# sensor_board_v0_9.net
KiCad netlist of a schematic drawn in EAGLE
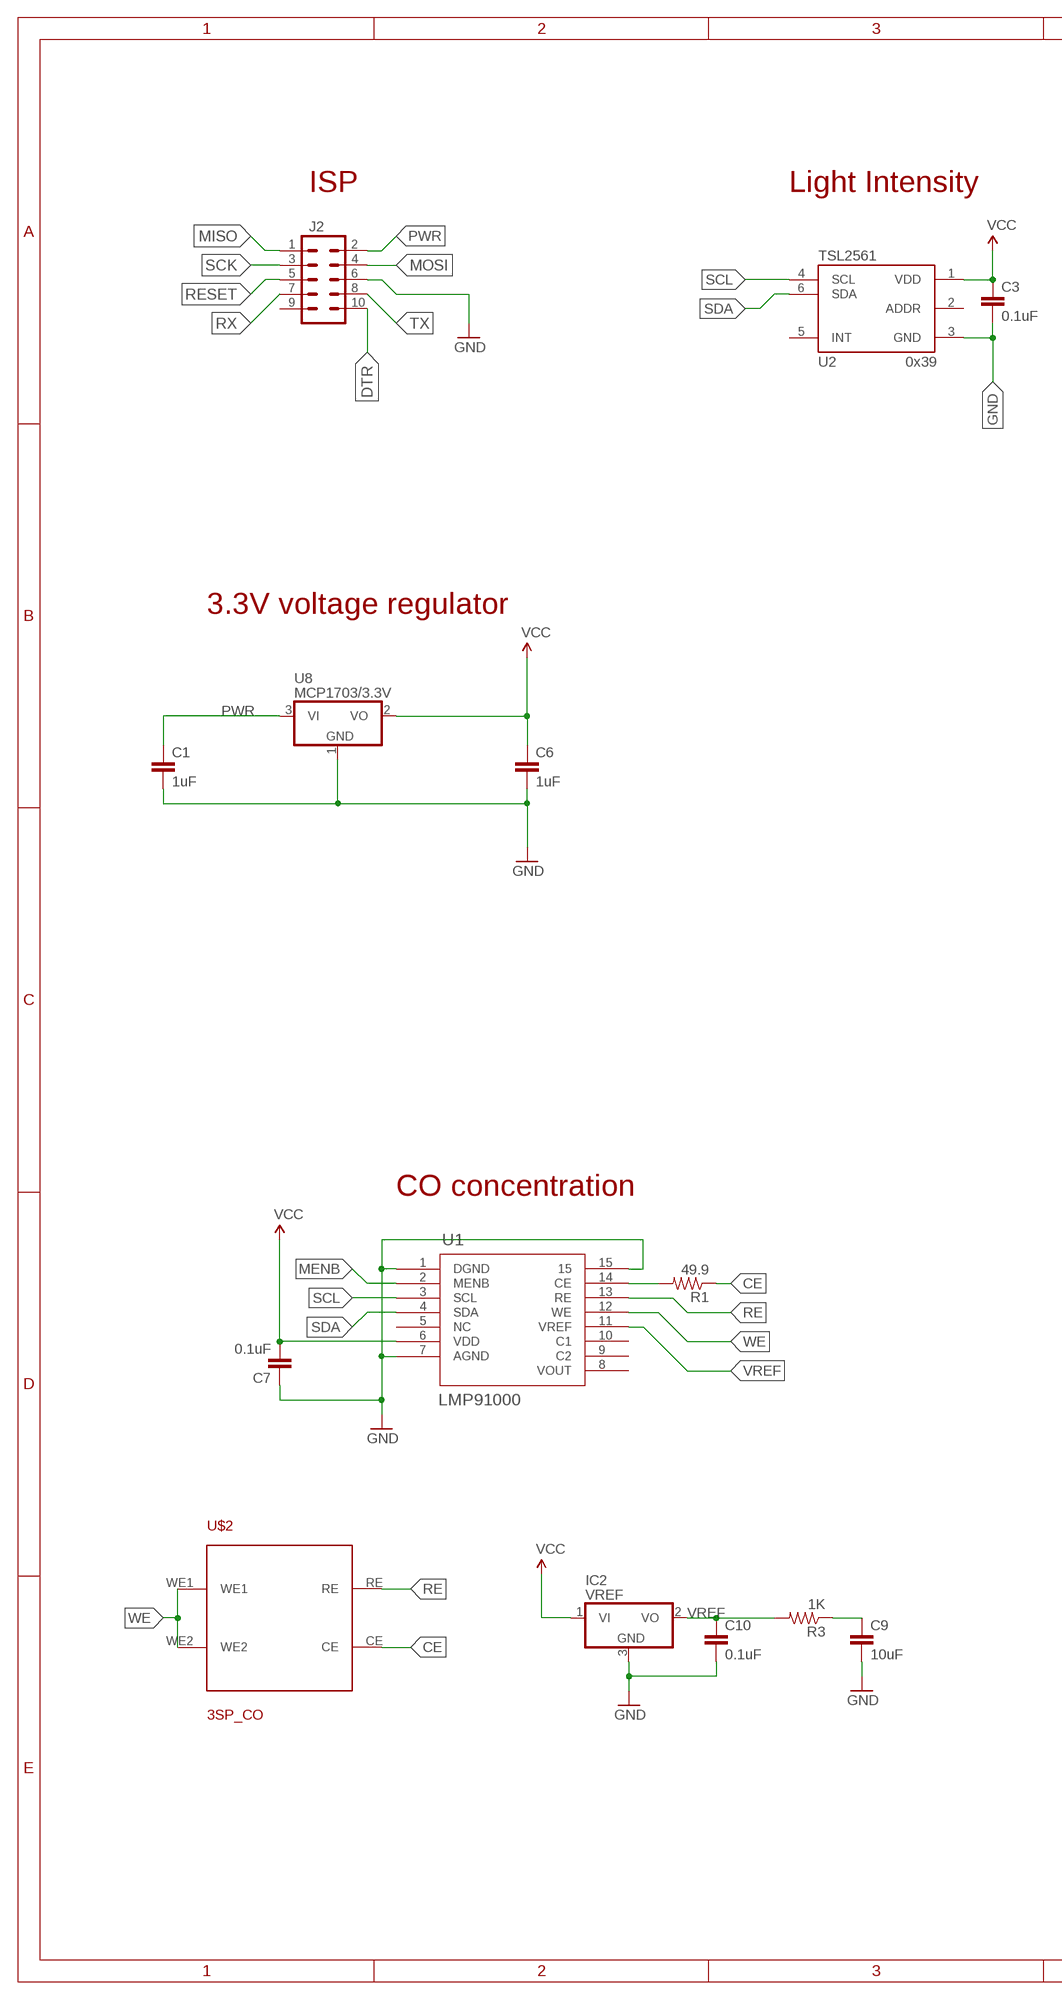
[diagram p0: schematic, sheet 1, part 1 of 2]
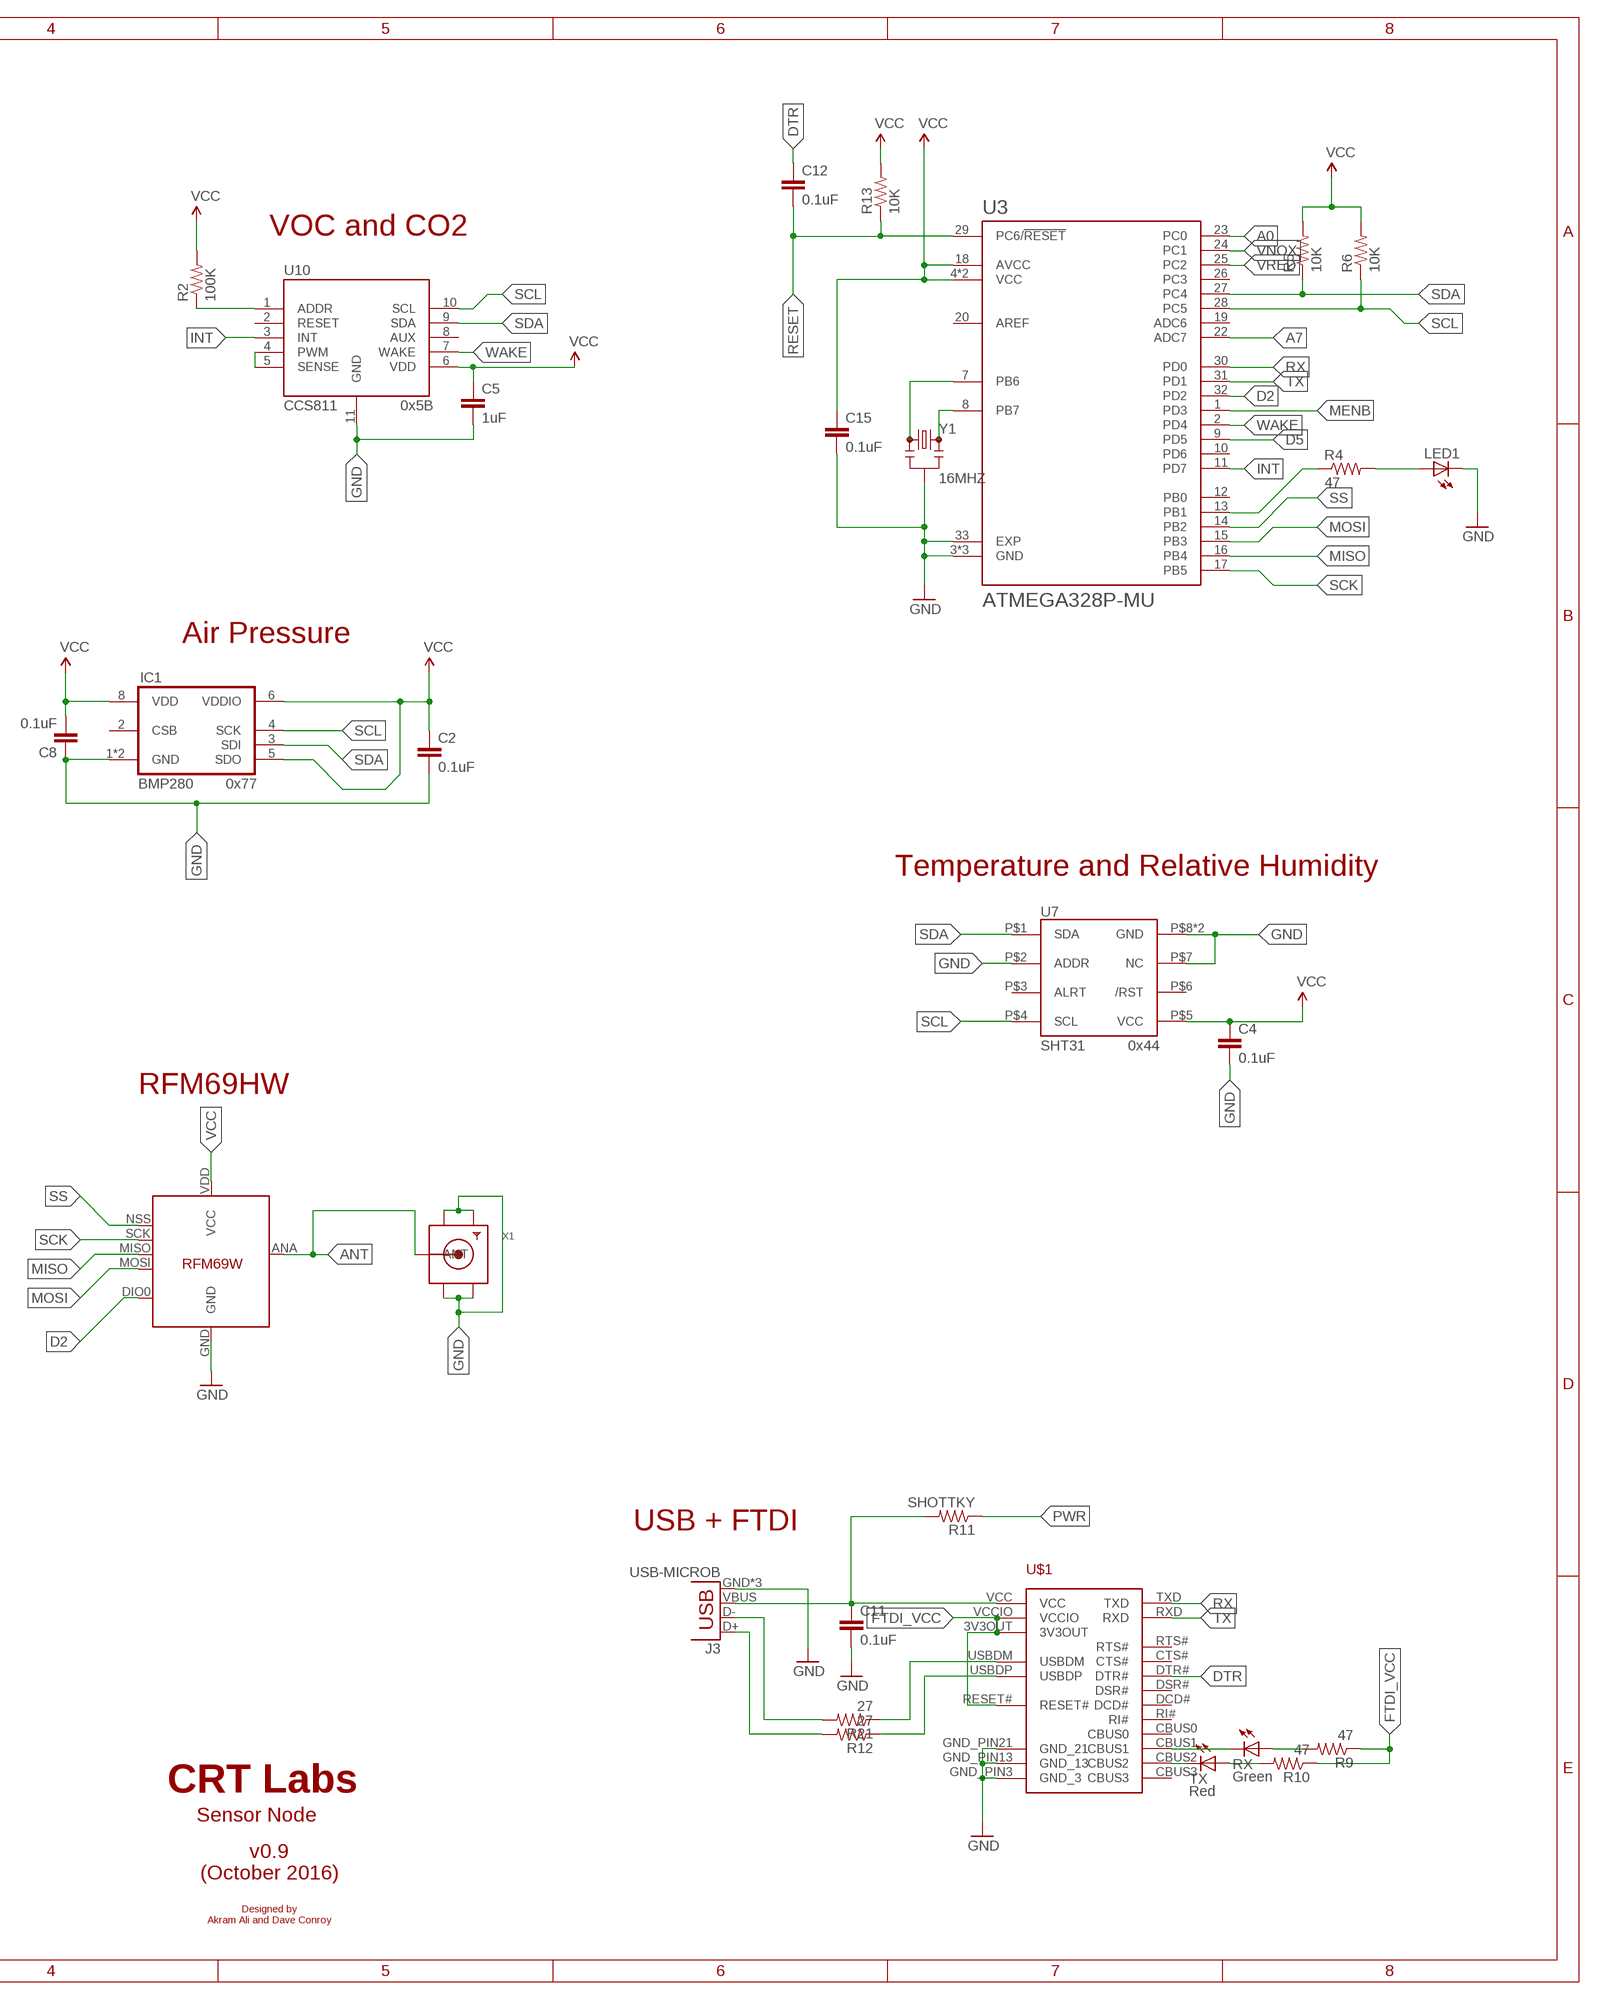
[diagram p1: schematic, sheet 1, part 2 of 2]

(export (version "E")
  (design (tool "Eeschema 10.0.6"))
  (components
    (comp (ref "C1")
      (value "1uF")
      (footprint "eagle-import:0805")
      (fields (field (name "MPN") "CC0805KKX7R7BB105"))
      (libsource (lib "eagle-import") (part "CAP0805"))
    )
    (comp (ref "C2")
      (value "0.1uF")
      (footprint "eagle-import:0805")
      (fields (field (name "MPN") "AC0805KRX7R9BB104"))
      (libsource (lib "eagle-import") (part "SparkFun-Passives_CAP0805"))
    )
    (comp (ref "C3")
      (value "0.1uF")
      (footprint "eagle-import:0805")
      (fields (field (name "MPN") "AC0805KRX7R9BB104"))
      (libsource (lib "eagle-import") (part "SparkFun-Passives_CAP0805"))
    )
    (comp (ref "C4")
      (value "0.1uF")
      (footprint "eagle-import:0805")
      (fields (field (name "MPN") "AC0805KRX7R9BB104"))
      (libsource (lib "eagle-import") (part "SparkFun-Passives_CAP0805"))
    )
    (comp (ref "C5")
      (value "1uF")
      (footprint "eagle-import:0805")
      (fields (field (name "MPN") "CC0805KKX7R7BB105"))
      (libsource (lib "eagle-import") (part "SparkFun-Passives_CAP0805"))
    )
    (comp (ref "C6")
      (value "1uF")
      (footprint "eagle-import:0805")
      (fields (field (name "MPN") "CC0805KKX7R7BB105"))
      (libsource (lib "eagle-import") (part "CAP0805"))
    )
    (comp (ref "C7")
      (value "0.1uF")
      (footprint "eagle-import:0805")
      (fields (field (name "MPN") "AC0805KRX7R9BB104"))
      (libsource (lib "eagle-import") (part "SparkFun-Passives_CAP0805"))
    )
    (comp (ref "C8")
      (value "0.1uF")
      (footprint "eagle-import:0805")
      (fields (field (name "MPN") "AC0805KRX7R9BB104"))
      (libsource (lib "eagle-import") (part "SparkFun-Passives_CAP0805"))
    )
    (comp (ref "C9")
      (value "10uF")
      (footprint "eagle-import:0805")
      (fields (field (name "MPN") "CC0805ZKY5V6BB106"))
      (libsource (lib "eagle-import") (part "SparkFun-Passives_CAP0805"))
    )
    (comp (ref "C10")
      (value "0.1uF")
      (footprint "eagle-import:0805")
      (fields (field (name "MPN") "AC0805KRX7R9BB104"))
      (libsource (lib "eagle-import") (part "SparkFun-Passives_CAP0805"))
    )
    (comp (ref "C11")
      (value "0.1uF")
      (footprint "eagle-import:0805")
      (fields (field (name "MPN") "AC0805KRX7R9BB104"))
      (libsource (lib "eagle-import") (part "CAP0805"))
    )
    (comp (ref "C12")
      (value "0.1uF")
      (footprint "eagle-import:0805")
      (fields (field (name "MPN") "AC0805KRX7R9BB104"))
      (libsource (lib "eagle-import") (part "SparkFun-Passives_CAP0805"))
    )
    (comp (ref "C15")
      (value "0.1uF")
      (footprint "eagle-import:0805")
      (fields (field (name "MPN") "AC0805KRX7R9BB104"))
      (libsource (lib "eagle-import") (part "SparkFun-Passives_CAP0805"))
    )
    (comp (ref "IC1")
      (value "BMP280")
      (footprint "eagle-import:BMP280")
      (libsource (lib "eagle-import") (part "BMP280"))
    )
    (comp (ref "IC2")
      (value "VREF")
      (footprint "eagle-import:SOT23")
      (fields (field (name "MPN") "ISL60002DIH320Z-TK"))
      (libsource (lib "eagle-import") (part "ISL60002DIH320ZCB"))
    )
    (comp (ref "J2")
      (value "M05X2PTH")
      (footprint "eagle-import:AVR_ICSP")
      (libsource (lib "eagle-import") (part "M05X2PTH"))
    )
    (comp (ref "J3")
      (value "USB-MICROB")
      (footprint "eagle-import:USB-MICROB")
      (fields (field (name "MPN") "CONN-09505"))
      (libsource (lib "eagle-import") (part "USB-MICROB"))
    )
    (comp (ref "LED1")
      (value "LEDCHIPLED_0805")
      (footprint "eagle-import:CHIPLED_0805")
      (fields (field (name "MPN") "150080BS75000"))
      (libsource (lib "eagle-import") (part "LEDCHIPLED_0805"))
    )
    (comp (ref "R1")
      (value "49.9")
      (footprint "eagle-import:0805")
      (fields (field (name "MPN") "RC0805FR-0749R9L"))
      (libsource (lib "eagle-import") (part "RESISTOR0805-RES"))
    )
    (comp (ref "R2")
      (value "100K")
      (footprint "eagle-import:0805")
      (fields (field (name "MPN") "311-100KCRCT-ND"))
      (libsource (lib "eagle-import") (part "RESISTOR0805-RES"))
    )
    (comp (ref "R3")
      (value "1K")
      (footprint "eagle-import:0805")
      (fields (field (name "MPN") "RC0805JR-071KL"))
      (libsource (lib "eagle-import") (part "RESISTOR0805-RES"))
    )
    (comp (ref "R4")
      (value "47")
      (footprint "eagle-import:0805")
      (fields (field (name "MPN") "RC0805JR-0747RL"))
      (libsource (lib "eagle-import") (part "SparkFun-Resistors_RESISTOR0805-RES"))
    )
    (comp (ref "R5")
      (value "10K")
      (footprint "eagle-import:0805")
      (fields (field (name "MPN") "RC0805JR-0710KL"))
      (libsource (lib "eagle-import") (part "SparkFun-Resistors_RESISTOR0805-RES"))
    )
    (comp (ref "R6")
      (value "10K")
      (footprint "eagle-import:0805")
      (fields (field (name "MPN") "RC0805JR-0710KL"))
      (libsource (lib "eagle-import") (part "SparkFun-Resistors_RESISTOR0805-RES"))
    )
    (comp (ref "R9")
      (value "47")
      (footprint "eagle-import:0805")
      (fields (field (name "MPN") "RC0805JR-0747RL"))
      (libsource (lib "eagle-import") (part "RESISTOR0805-RES"))
    )
    (comp (ref "R10")
      (value "47")
      (footprint "eagle-import:0805")
      (fields (field (name "MPN") "RC0805JR-0747RL"))
      (libsource (lib "eagle-import") (part "RESISTOR0805-RES"))
    )
    (comp (ref "R11")
      (value "SHOTTKY")
      (footprint "eagle-import:0805")
      (fields (field (name "MPN") "SD0805S020S0R5"))
      (libsource (lib "eagle-import") (part "RESISTOR0805-RES"))
    )
    (comp (ref "R12")
      (value "27")
      (footprint "eagle-import:0805")
      (fields (field (name "MPN") "RC0805FR-0727RL"))
      (libsource (lib "eagle-import") (part "RESISTOR0805-RES"))
    )
    (comp (ref "R13")
      (value "10K")
      (footprint "eagle-import:0805")
      (fields (field (name "MPN") "RC0805JR-0710KL"))
      (libsource (lib "eagle-import") (part "RESISTOR0805-RES"))
    )
    (comp (ref "R21")
      (value "27")
      (footprint "eagle-import:0805")
      (fields (field (name "MPN") "RC0805FR-0727RL"))
      (libsource (lib "eagle-import") (part "RESISTOR0805-RES"))
    )
    (comp (ref "RX")
      (value "Green")
      (footprint "eagle-import:CHIPLED_0805")
      (fields (field (name "MPN") "LG R971-KN-1"))
      (libsource (lib "eagle-import") (part "LEDCHIPLED_0805"))
    )
    (comp (ref "TX")
      (value "Red")
      (footprint "eagle-import:CHIPLED_0805")
      (fields (field (name "MPN") "LH R974-LP-1"))
      (libsource (lib "eagle-import") (part "LEDCHIPLED_0805"))
    )
    (comp (ref "U$1")
      (value "FT231XQ-R")
      (footprint "eagle-import:FTDI_FT231XQ-R_PACKAGE")
      (libsource (lib "eagle-import") (part "FT231XQ-R"))
    )
    (comp (ref "U$2")
      (value "3SP_CO")
      (footprint "eagle-import:3SP_CO_PIN_PACKAGE")
      (fields (field (name "MPN") "3SP CO"))
      (libsource (lib "eagle-import") (part "3SP_CO"))
    )
    (comp (ref "U1")
      (value "LMP91000")
      (footprint "eagle-import:SDA14B")
      (fields
        (field (name "MANUFACTURER") "Texas Instruments")
        (field (name "MANUFACTURER_PART_NUMBER") "lmp91000_nhl_14")
      )
      (libsource (lib "eagle-import") (part "LMP91000_NHL_14"))
    )
    (comp (ref "U2")
      (value "TSL2561")
      (footprint "eagle-import:FN-6")
      (fields (field (name "MPN") "TSL2561FN"))
      (libsource (lib "eagle-import") (part "TSL2561FN"))
    )
    (comp (ref "U3")
      (value "ATMEGA328P-MU")
      (footprint "eagle-import:QFN50P500X500X100-33N")
      (fields (field (name "MF") "Atmel"))
      (libsource (lib "eagle-import") (part "ATMEGA328P-MU"))
    )
    (comp (ref "U7")
      (value "SHT31")
      (footprint "eagle-import:SHT3X")
      (fields (field (name "MPN") "SHT31-DIS-B"))
      (libsource (lib "eagle-import") (part "SHT31-DIS"))
    )
    (comp (ref "U8")
      (value "MCP1703/3.3V")
      (footprint "eagle-import:SOT23")
      (fields (field (name "MPN") "MCP1703T-2502E/CB"))
      (libsource (lib "eagle-import") (part "MCP1703CB"))
    )
    (comp (ref "U10")
      (value "CCS811")
      (footprint "eagle-import:LGA")
      (libsource (lib "eagle-import") (part "CCS811-I2C"))
    )
    (comp (ref "U11")
      (value "RFM69HW")
      (footprint "eagle-import:LOWPOWERLAB_RFM69W-MINPADS")
      (libsource (lib "eagle-import") (part "LOWPOWERLAB_RFM69"))
    )
    (comp (ref "X1")
      (value "SMACONNECTOR_EDGE")
      (footprint "eagle-import:SMA_EDGELAUNCH")
      (fields (field (name "MPN") "WRL-00593"))
      (libsource (lib "eagle-import") (part "SMACONNECTOR_EDGE"))
    )
    (comp (ref "Y1")
      (value "16MHZ")
      (footprint "eagle-import:RESONATOR-SMD")
      (fields (field (name "MPN") "CSTCE16M0V53-R0"))
      (libsource (lib "eagle-import") (part "RESONATOR16MHZ"))
    )
  )
  (nets
    (net (code "1") (name "A0") (class "Default")
      (node (ref "U3") (pin "23") (pinfunction "PC0_23") (pintype "bidirectional"))
    )
    (net (code "2") (name "A7") (class "Default")
      (node (ref "U3") (pin "22") (pinfunction "ADC7_22") (pintype "bidirectional"))
    )
    (net (code "3") (name "ANT") (class "Default")
      (node (ref "U11") (pin "ANA") (pinfunction "ANT_ANA") (pintype "passive"))
      (node (ref "X1") (pin "P") (pinfunction "ANT_P") (pintype "bidirectional"))
    )
    (net (code "4") (name "CE") (class "Default")
      (node (ref "R1") (pin "1") (pinfunction "1_1") (pintype "passive"))
      (node (ref "U$2") (pin "CE") (pinfunction "CE_CE") (pintype "bidirectional"))
    )
    (net (code "5") (name "D2") (class "Default")
      (node (ref "U11") (pin "DIO0") (pinfunction "DIO0_DIO0") (pintype "open_collector"))
      (node (ref "U3") (pin "32") (pinfunction "PD2_32") (pintype "bidirectional"))
    )
    (net (code "6") (name "D5") (class "Default")
      (node (ref "U3") (pin "9") (pinfunction "PD5_9") (pintype "bidirectional"))
    )
    (net (code "7") (name "DTR") (class "Default")
      (node (ref "C12") (pin "1") (pinfunction "1_1") (pintype "passive"))
      (node (ref "J2") (pin "10") (pinfunction "10_10") (pintype "passive"))
      (node (ref "U$1") (pin "DTR#") (pinfunction "DTR#_DTR#") (pintype "bidirectional"))
    )
    (net (code "8") (name "FTDI_VCC") (class "Default")
      (node (ref "R10") (pin "1") (pinfunction "1_1") (pintype "passive"))
      (node (ref "R9") (pin "1") (pinfunction "1_1") (pintype "passive"))
      (node (ref "U$1") (pin "3V3OUT") (pinfunction "3V3OUT_3V3OUT") (pintype "bidirectional"))
      (node (ref "U$1") (pin "RESET#") (pinfunction "RESET#_RESET#") (pintype "bidirectional"))
      (node (ref "U$1") (pin "VCCIO") (pinfunction "VCCIO_VCCIO") (pintype "bidirectional"))
    )
    (net (code "9") (name "GND") (class "Default")
      (node (ref "C1") (pin "2") (pinfunction "2_2") (pintype "passive"))
      (node (ref "C10") (pin "2") (pinfunction "2_2") (pintype "passive"))
      (node (ref "C11") (pin "2") (pinfunction "2_2") (pintype "passive"))
      (node (ref "C15") (pin "2") (pinfunction "2_2") (pintype "passive"))
      (node (ref "C2") (pin "2") (pinfunction "2_2") (pintype "passive"))
      (node (ref "C3") (pin "2") (pinfunction "2_2") (pintype "passive"))
      (node (ref "C4") (pin "2") (pinfunction "2_2") (pintype "passive"))
      (node (ref "C5") (pin "2") (pinfunction "2_2") (pintype "passive"))
      (node (ref "C6") (pin "2") (pinfunction "2_2") (pintype "passive"))
      (node (ref "C7") (pin "1") (pinfunction "1_1") (pintype "passive"))
      (node (ref "C8") (pin "1") (pinfunction "1_1") (pintype "passive"))
      (node (ref "C9") (pin "2") (pinfunction "2_2") (pintype "passive"))
      (node (ref "IC1") (pin "1") (pinfunction "GND_1") (pintype "power_in"))
      (node (ref "IC1") (pin "7") (pinfunction "GND_7") (pintype "power_in"))
      (node (ref "IC2") (pin "3") (pinfunction "GND_3") (pintype "passive"))
      (node (ref "J2") (pin "6") (pinfunction "6_6") (pintype "passive"))
      (node (ref "J3") (pin "GND") (pinfunction "GND_GND") (pintype "bidirectional"))
      (node (ref "J3") (pin "MT1") (pinfunction "GND_MT1") (pintype "bidirectional"))
      (node (ref "J3") (pin "MT2") (pinfunction "GND_MT2") (pintype "bidirectional"))
      (node (ref "LED1") (pin "C") (pinfunction "C_C") (pintype "passive"))
      (node (ref "U$1") (pin "GND_PIN13") (pinfunction "GND_13_GND_PIN13") (pintype "bidirectional"))
      (node (ref "U$1") (pin "GND_PIN21") (pinfunction "GND_21_GND_PIN21") (pintype "bidirectional"))
      (node (ref "U$1") (pin "GND_PIN3") (pinfunction "GND_3_GND_PIN3") (pintype "bidirectional"))
      (node (ref "U1") (pin "1") (pinfunction "DGND_1") (pintype "power_in"))
      (node (ref "U1") (pin "15") (pinfunction "15_15") (pintype "passive"))
      (node (ref "U1") (pin "7") (pinfunction "AGND_7") (pintype "power_in"))
      (node (ref "U10") (pin "11") (pinfunction "GND_11") (pintype "bidirectional"))
      (node (ref "U11") (pin "GND") (pinfunction "GND_GND") (pintype "power_in"))
      (node (ref "U2") (pin "3") (pinfunction "GND_3") (pintype "power_in"))
      (node (ref "U3") (pin "21") (pinfunction "GND_21") (pintype "power_in"))
      (node (ref "U3") (pin "3") (pinfunction "GND_3") (pintype "power_in"))
      (node (ref "U3") (pin "33") (pinfunction "EXP_33") (pintype "power_in"))
      (node (ref "U3") (pin "5") (pinfunction "GND_5") (pintype "power_in"))
      (node (ref "U7") (pin "P$2") (pinfunction "ADDR_P$2") (pintype "bidirectional"))
      (node (ref "U7") (pin "P$7") (pinfunction "NC_P$7") (pintype "bidirectional"))
      (node (ref "U7") (pin "P$8") (pinfunction "GND_P$8") (pintype "bidirectional"))
      (node (ref "U7") (pin "PAD") (pinfunction "GND_PAD") (pintype "bidirectional"))
      (node (ref "U8") (pin "1") (pinfunction "GND_1") (pintype "passive"))
      (node (ref "X1") (pin "GND@1") (pinfunction "GND4_GND@1") (pintype "power_in"))
      (node (ref "X1") (pin "GND@2") (pinfunction "GND3_GND@2") (pintype "power_in"))
      (node (ref "X1") (pin "GND@3") (pinfunction "GND2_GND@3") (pintype "power_in"))
      (node (ref "X1") (pin "GND@4") (pinfunction "GND1_GND@4") (pintype "power_in"))
      (node (ref "Y1") (pin "2") (pinfunction "2_2") (pintype "passive"))
    )
    (net (code "10") (name "INT") (class "Default")
      (node (ref "U10") (pin "3") (pinfunction "INT_3") (pintype "bidirectional"))
      (node (ref "U3") (pin "11") (pinfunction "PD7_11") (pintype "bidirectional"))
    )
    (net (code "11") (name "MENB") (class "Default")
      (node (ref "U1") (pin "2") (pinfunction "MENB_2") (pintype "passive"))
      (node (ref "U3") (pin "1") (pinfunction "PD3_1") (pintype "bidirectional"))
    )
    (net (code "12") (name "MISO") (class "Default")
      (node (ref "J2") (pin "1") (pinfunction "1_1") (pintype "passive"))
      (node (ref "U11") (pin "MISO") (pinfunction "MISO_MISO") (pintype "input"))
      (node (ref "U3") (pin "16") (pinfunction "PB4_16") (pintype "bidirectional"))
    )
    (net (code "13") (name "MOSI") (class "Default")
      (node (ref "J2") (pin "4") (pinfunction "4_4") (pintype "passive"))
      (node (ref "U11") (pin "MOSI") (pinfunction "MOSI_MOSI") (pintype "output"))
      (node (ref "U3") (pin "15") (pinfunction "PB3_15") (pintype "bidirectional"))
    )
    (net (code "14") (name "Net-(C9-Pad1)") (class "Default")
      (node (ref "C9") (pin "1") (pinfunction "1_1") (pintype "passive"))
      (node (ref "R3") (pin "1") (pinfunction "1_1") (pintype "passive"))
    )
    (net (code "15") (name "Net-(C11-Pad1)") (class "Default")
      (node (ref "C11") (pin "1") (pinfunction "1_1") (pintype "passive"))
      (node (ref "J3") (pin "VBUS") (pinfunction "VBUS_VBUS") (pintype "bidirectional"))
      (node (ref "R11") (pin "2") (pinfunction "2_2") (pintype "passive"))
      (node (ref "U$1") (pin "VCC") (pinfunction "VCC_VCC") (pintype "bidirectional"))
    )
    (net (code "16") (name "Net-(J3-PadD+)") (class "Default")
      (node (ref "J3") (pin "D+") (pinfunction "D+_D+") (pintype "bidirectional"))
      (node (ref "R12") (pin "2") (pinfunction "2_2") (pintype "passive"))
    )
    (net (code "17") (name "Net-(J3-PadD-)") (class "Default")
      (node (ref "J3") (pin "D-") (pinfunction "D-_D-") (pintype "bidirectional"))
      (node (ref "R21") (pin "2") (pinfunction "2_2") (pintype "passive"))
    )
    (net (code "18") (name "Net-(LED1-PadA)") (class "Default")
      (node (ref "LED1") (pin "A") (pinfunction "A_A") (pintype "passive"))
      (node (ref "R4") (pin "2") (pinfunction "2_2") (pintype "passive"))
    )
    (net (code "19") (name "Net-(R9-Pad2)") (class "Default")
      (node (ref "R9") (pin "2") (pinfunction "2_2") (pintype "passive"))
      (node (ref "RX") (pin "A") (pinfunction "A_A") (pintype "passive"))
    )
    (net (code "20") (name "Net-(R10-Pad2)") (class "Default")
      (node (ref "R10") (pin "2") (pinfunction "2_2") (pintype "passive"))
      (node (ref "TX") (pin "A") (pinfunction "A_A") (pintype "passive"))
    )
    (net (code "21") (name "Net-(R12-Pad1)") (class "Default")
      (node (ref "R12") (pin "1") (pinfunction "1_1") (pintype "passive"))
      (node (ref "U$1") (pin "USBDP") (pinfunction "USBDP_USBDP") (pintype "bidirectional"))
    )
    (net (code "22") (name "Net-(R21-Pad1)") (class "Default")
      (node (ref "R21") (pin "1") (pinfunction "1_1") (pintype "passive"))
      (node (ref "U$1") (pin "USBDM") (pinfunction "USBDM_USBDM") (pintype "bidirectional"))
    )
    (net (code "23") (name "Net-(RX-PadC)") (class "Default")
      (node (ref "RX") (pin "C") (pinfunction "C_C") (pintype "passive"))
      (node (ref "U$1") (pin "CBUS1") (pinfunction "CBUS1_CBUS1") (pintype "bidirectional"))
    )
    (net (code "24") (name "Net-(TX-PadC)") (class "Default")
      (node (ref "TX") (pin "C") (pinfunction "C_C") (pintype "passive"))
      (node (ref "U$1") (pin "CBUS2") (pinfunction "CBUS2_CBUS2") (pintype "bidirectional"))
    )
    (net (code "25") (name "Net-(U1-CE)") (class "Default")
      (node (ref "R1") (pin "2") (pinfunction "2_2") (pintype "passive"))
      (node (ref "U1") (pin "14") (pinfunction "CE_14") (pintype "output"))
    )
    (net (code "26") (name "Net-(U3-PB1)") (class "Default")
      (node (ref "R4") (pin "1") (pinfunction "1_1") (pintype "passive"))
      (node (ref "U3") (pin "13") (pinfunction "PB1_13") (pintype "bidirectional"))
    )
    (net (code "27") (name "Net-(U3-PB6)") (class "Default")
      (node (ref "U3") (pin "7") (pinfunction "PB6_7") (pintype "bidirectional"))
      (node (ref "Y1") (pin "1") (pinfunction "1_1") (pintype "passive"))
    )
    (net (code "28") (name "Net-(U3-PB7)") (class "Default")
      (node (ref "U3") (pin "8") (pinfunction "PB7_8") (pintype "bidirectional"))
      (node (ref "Y1") (pin "3") (pinfunction "3_3") (pintype "passive"))
    )
    (net (code "29") (name "Net-(U10-ADDR)") (class "Default")
      (node (ref "R2") (pin "1") (pinfunction "1_1") (pintype "passive"))
      (node (ref "U10") (pin "1") (pinfunction "ADDR_1") (pintype "bidirectional"))
    )
    (net (code "30") (name "Net-(U10-PWM)") (class "Default")
      (node (ref "U10") (pin "4") (pinfunction "PWM_4") (pintype "bidirectional"))
      (node (ref "U10") (pin "5") (pinfunction "SENSE_5") (pintype "bidirectional"))
    )
    (net (code "31") (name "PWR") (class "Default")
      (node (ref "C1") (pin "1") (pinfunction "1_1") (pintype "passive"))
      (node (ref "J2") (pin "2") (pinfunction "2_2") (pintype "passive"))
      (node (ref "R11") (pin "1") (pinfunction "1_1") (pintype "passive"))
      (node (ref "U8") (pin "3") (pinfunction "VI_3") (pintype "input"))
    )
    (net (code "32") (name "RE") (class "Default")
      (node (ref "U$2") (pin "RE") (pinfunction "RE_RE") (pintype "bidirectional"))
      (node (ref "U1") (pin "13") (pinfunction "RE_13") (pintype "input"))
    )
    (net (code "33") (name "RESET") (class "Default")
      (node (ref "C12") (pin "2") (pinfunction "2_2") (pintype "passive"))
      (node (ref "J2") (pin "5") (pinfunction "5_5") (pintype "passive"))
      (node (ref "R13") (pin "1") (pinfunction "1_1") (pintype "passive"))
      (node (ref "U3") (pin "29") (pinfunction "PC6/~{RESET}_29") (pintype "bidirectional"))
    )
    (net (code "34") (name "RX") (class "Default")
      (node (ref "J2") (pin "7") (pinfunction "7_7") (pintype "passive"))
      (node (ref "U$1") (pin "TXD") (pinfunction "TXD_TXD") (pintype "bidirectional"))
      (node (ref "U3") (pin "30") (pinfunction "PD0_30") (pintype "bidirectional"))
    )
    (net (code "35") (name "SCK") (class "Default")
      (node (ref "J2") (pin "3") (pinfunction "3_3") (pintype "passive"))
      (node (ref "U11") (pin "SCK") (pinfunction "SCK_SCK") (pintype "input"))
      (node (ref "U3") (pin "17") (pinfunction "PB5_17") (pintype "bidirectional"))
    )
    (net (code "36") (name "SCL") (class "Default")
      (node (ref "IC1") (pin "4") (pinfunction "SCK_4") (pintype "bidirectional"))
      (node (ref "R6") (pin "1") (pinfunction "1_1") (pintype "passive"))
      (node (ref "U1") (pin "3") (pinfunction "SCL_3") (pintype "passive"))
      (node (ref "U10") (pin "10") (pinfunction "SCL_10") (pintype "bidirectional"))
      (node (ref "U2") (pin "4") (pinfunction "SCL_4") (pintype "input"))
      (node (ref "U3") (pin "28") (pinfunction "PC5_28") (pintype "bidirectional"))
      (node (ref "U7") (pin "P$4") (pinfunction "SCL_P$4") (pintype "bidirectional"))
    )
    (net (code "37") (name "SDA") (class "Default")
      (node (ref "IC1") (pin "3") (pinfunction "SDI_3") (pintype "bidirectional"))
      (node (ref "R5") (pin "1") (pinfunction "1_1") (pintype "passive"))
      (node (ref "U1") (pin "4") (pinfunction "SDA_4") (pintype "passive"))
      (node (ref "U10") (pin "9") (pinfunction "SDA_9") (pintype "bidirectional"))
      (node (ref "U2") (pin "6") (pinfunction "SDA_6") (pintype "bidirectional"))
      (node (ref "U3") (pin "27") (pinfunction "PC4_27") (pintype "bidirectional"))
      (node (ref "U7") (pin "P$1") (pinfunction "SDA_P$1") (pintype "bidirectional"))
    )
    (net (code "38") (name "SS") (class "Default")
      (node (ref "U11") (pin "NSS") (pinfunction "SEL_NSS") (pintype "input"))
      (node (ref "U3") (pin "14") (pinfunction "PB2_14") (pintype "bidirectional"))
    )
    (net (code "39") (name "TX") (class "Default")
      (node (ref "J2") (pin "8") (pinfunction "8_8") (pintype "passive"))
      (node (ref "U$1") (pin "RXD") (pinfunction "RXD_RXD") (pintype "bidirectional"))
      (node (ref "U3") (pin "31") (pinfunction "PD1_31") (pintype "bidirectional"))
    )
    (net (code "40") (name "VCC") (class "Default")
      (node (ref "C15") (pin "1") (pinfunction "1_1") (pintype "passive"))
      (node (ref "C2") (pin "1") (pinfunction "1_1") (pintype "passive"))
      (node (ref "C3") (pin "1") (pinfunction "1_1") (pintype "passive"))
      (node (ref "C4") (pin "1") (pinfunction "1_1") (pintype "passive"))
      (node (ref "C5") (pin "1") (pinfunction "1_1") (pintype "passive"))
      (node (ref "C6") (pin "1") (pinfunction "1_1") (pintype "passive"))
      (node (ref "C7") (pin "2") (pinfunction "2_2") (pintype "passive"))
      (node (ref "C8") (pin "2") (pinfunction "2_2") (pintype "passive"))
      (node (ref "IC1") (pin "5") (pinfunction "SDO_5") (pintype "input"))
      (node (ref "IC1") (pin "6") (pinfunction "VDDIO_6") (pintype "power_in"))
      (node (ref "IC1") (pin "8") (pinfunction "VDD_8") (pintype "power_in"))
      (node (ref "IC2") (pin "1") (pinfunction "VI_1") (pintype "input"))
      (node (ref "R13") (pin "2") (pinfunction "2_2") (pintype "passive"))
      (node (ref "R2") (pin "2") (pinfunction "2_2") (pintype "passive"))
      (node (ref "R5") (pin "2") (pinfunction "2_2") (pintype "passive"))
      (node (ref "R6") (pin "2") (pinfunction "2_2") (pintype "passive"))
      (node (ref "U1") (pin "6") (pinfunction "VDD_6") (pintype "power_in"))
      (node (ref "U10") (pin "6") (pinfunction "VDD_6") (pintype "bidirectional"))
      (node (ref "U11") (pin "VDD") (pinfunction "VCC_VDD") (pintype "power_in"))
      (node (ref "U2") (pin "1") (pinfunction "VDD_1") (pintype "power_in"))
      (node (ref "U3") (pin "18") (pinfunction "AVCC_18") (pintype "power_in"))
      (node (ref "U3") (pin "4") (pinfunction "VCC_4") (pintype "power_in"))
      (node (ref "U3") (pin "6") (pinfunction "VCC_6") (pintype "power_in"))
      (node (ref "U7") (pin "P$5") (pinfunction "VCC_P$5") (pintype "bidirectional"))
      (node (ref "U8") (pin "2") (pinfunction "VO_2") (pintype "passive"))
    )
    (net (code "41") (name "VNOX") (class "Default")
      (node (ref "U3") (pin "24") (pinfunction "PC1_24") (pintype "bidirectional"))
    )
    (net (code "42") (name "VRED") (class "Default")
      (node (ref "U3") (pin "25") (pinfunction "PC2_25") (pintype "bidirectional"))
    )
    (net (code "43") (name "VREF") (class "Default")
      (node (ref "C10") (pin "1") (pinfunction "1_1") (pintype "passive"))
      (node (ref "IC2") (pin "2") (pinfunction "VO_2") (pintype "passive"))
      (node (ref "R3") (pin "2") (pinfunction "2_2") (pintype "passive"))
      (node (ref "U1") (pin "11") (pinfunction "VREF_11") (pintype "input"))
    )
    (net (code "44") (name "WAKE") (class "Default")
      (node (ref "U10") (pin "7") (pinfunction "WAKE_7") (pintype "bidirectional"))
      (node (ref "U3") (pin "2") (pinfunction "PD4_2") (pintype "bidirectional"))
    )
    (net (code "45") (name "WE") (class "Default")
      (node (ref "U$2") (pin "WE1") (pinfunction "WE1_WE1") (pintype "bidirectional"))
      (node (ref "U$2") (pin "WE2") (pinfunction "WE2_WE2") (pintype "bidirectional"))
      (node (ref "U1") (pin "12") (pinfunction "WE_12") (pintype "output"))
    )
    (net (code "46") (name "unconnected-(IC1-CSB-Pad2)") (class "Default")
      (node (ref "IC1") (pin "2") (pinfunction "CSB_2") (pintype "input"))
    )
    (net (code "47") (name "unconnected-(J2-Pad9)") (class "Default")
      (node (ref "J2") (pin "9") (pinfunction "9_9") (pintype "passive"))
    )
    (net (code "48") (name "unconnected-(U$1-PadCBUS0)") (class "Default")
      (node (ref "U$1") (pin "CBUS0") (pinfunction "CBUS0_CBUS0") (pintype "bidirectional"))
    )
    (net (code "49") (name "unconnected-(U$1-PadCBUS3)") (class "Default")
      (node (ref "U$1") (pin "CBUS3") (pinfunction "CBUS3_CBUS3") (pintype "bidirectional"))
    )
    (net (code "50") (name "unconnected-(U$1-PadCTS#)") (class "Default")
      (node (ref "U$1") (pin "CTS#") (pinfunction "CTS#_CTS#") (pintype "bidirectional"))
    )
    (net (code "51") (name "unconnected-(U$1-PadDCD#)") (class "Default")
      (node (ref "U$1") (pin "DCD#") (pinfunction "DCD#_DCD#") (pintype "bidirectional"))
    )
    (net (code "52") (name "unconnected-(U$1-PadDSR#)") (class "Default")
      (node (ref "U$1") (pin "DSR#") (pinfunction "DSR#_DSR#") (pintype "bidirectional"))
    )
    (net (code "53") (name "unconnected-(U$1-PadRI#)") (class "Default")
      (node (ref "U$1") (pin "RI#") (pinfunction "RI#_RI#") (pintype "bidirectional"))
    )
    (net (code "54") (name "unconnected-(U$1-PadRTS#)") (class "Default")
      (node (ref "U$1") (pin "RTS#") (pinfunction "RTS#_RTS#") (pintype "bidirectional"))
    )
    (net (code "55") (name "unconnected-(U1-C1-Pad10)") (class "Default")
      (node (ref "U1") (pin "10") (pinfunction "C1_10") (pintype "passive"))
    )
    (net (code "56") (name "unconnected-(U1-C2-Pad9)") (class "Default")
      (node (ref "U1") (pin "9") (pinfunction "C2_9") (pintype "passive"))
    )
    (net (code "57") (name "unconnected-(U1-NC-Pad5)") (class "Default")
      (node (ref "U1") (pin "5") (pinfunction "NC_5") (pintype "no_connect"))
    )
    (net (code "58") (name "unconnected-(U1-VOUT-Pad8)") (class "Default")
      (node (ref "U1") (pin "8") (pinfunction "VOUT_8") (pintype "output"))
    )
    (net (code "59") (name "unconnected-(U2-ADDR-Pad2)") (class "Default")
      (node (ref "U2") (pin "2") (pinfunction "ADDR_2") (pintype "input"))
    )
    (net (code "60") (name "unconnected-(U2-INT-Pad5)") (class "Default")
      (node (ref "U2") (pin "5") (pinfunction "INT_5") (pintype "output"))
    )
    (net (code "61") (name "unconnected-(U3-ADC6-Pad19)") (class "Default")
      (node (ref "U3") (pin "19") (pinfunction "ADC6_19") (pintype "bidirectional"))
    )
    (net (code "62") (name "unconnected-(U3-AREF-Pad20)") (class "Default")
      (node (ref "U3") (pin "20") (pinfunction "AREF_20") (pintype "input"))
    )
    (net (code "63") (name "unconnected-(U3-PB0-Pad12)") (class "Default")
      (node (ref "U3") (pin "12") (pinfunction "PB0_12") (pintype "bidirectional"))
    )
    (net (code "64") (name "unconnected-(U3-PC3-Pad26)") (class "Default")
      (node (ref "U3") (pin "26") (pinfunction "PC3_26") (pintype "bidirectional"))
    )
    (net (code "65") (name "unconnected-(U3-PD6-Pad10)") (class "Default")
      (node (ref "U3") (pin "10") (pinfunction "PD6_10") (pintype "bidirectional"))
    )
    (net (code "66") (name "unconnected-(U7-ALRT-PadP$3)") (class "Default")
      (node (ref "U7") (pin "P$3") (pinfunction "ALRT_P$3") (pintype "bidirectional"))
    )
    (net (code "67") (name "unconnected-(U7-{slash}RST-PadP$6)") (class "Default")
      (node (ref "U7") (pin "P$6") (pinfunction "/RST_P$6") (pintype "bidirectional"))
    )
    (net (code "68") (name "unconnected-(U10-AUX-Pad8)") (class "Default")
      (node (ref "U10") (pin "8") (pinfunction "AUX_8") (pintype "bidirectional"))
    )
    (net (code "69") (name "unconnected-(U10-RESET-Pad2)") (class "Default")
      (node (ref "U10") (pin "2") (pinfunction "RESET_2") (pintype "bidirectional"))
    )
  )
)
